# Power_Suply.net
KiCad netlist of a schematic drawn in Altium Designer
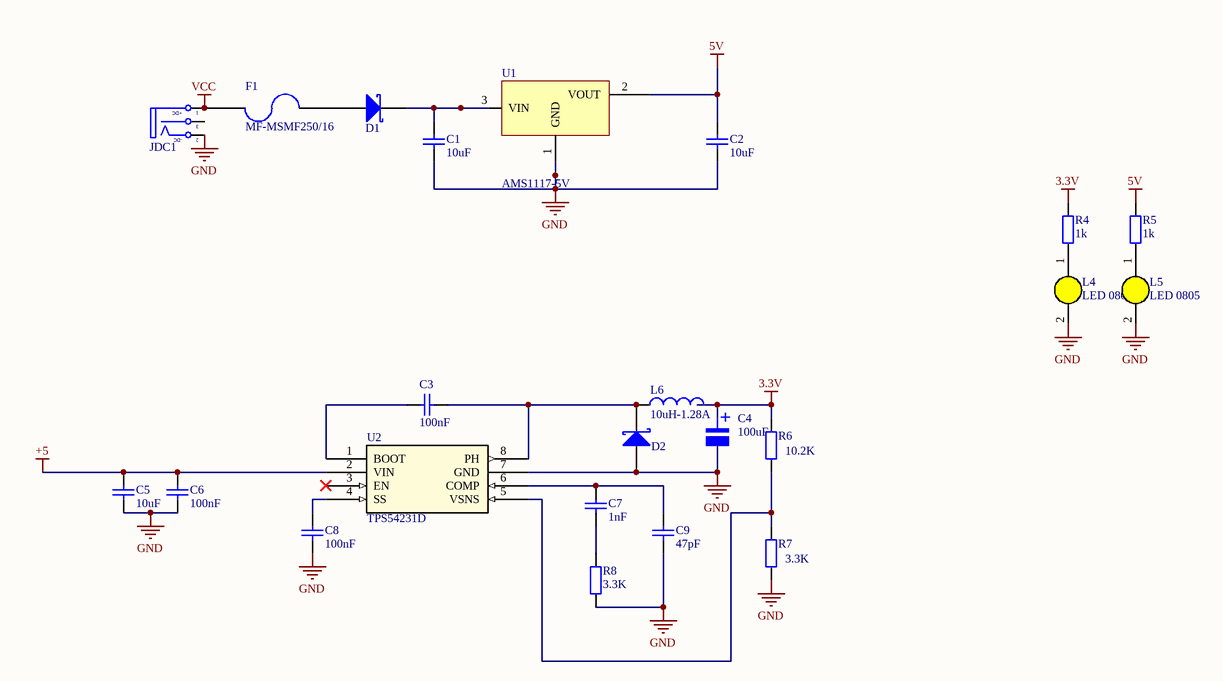
[diagram p0: Power Suply.SchDoc]

(export (version "E")
  (design (tool "Eeschema 10.0.6"))
  (components
    (comp (ref "C1")
      (value "10uF")
      (footprint "tu 0805")
      (description "Dán")
      (libsource (lib "Tu dien") (part "Tu 0805 101 50V 20%"))
    )
    (comp (ref "C2")
      (value "10uF")
      (footprint "tu 0805")
      (description "Dán")
      (libsource (lib "Tu dien") (part "Tu 0805 101 50V 20%"))
    )
    (comp (ref "C3")
      (value "100nF")
      (footprint "tu 0805")
      (description "Dán")
      (libsource (lib "Tu dien") (part "Tu 0805 106 16V 10%"))
    )
    (comp (ref "C4")
      (value "100uF")
      (footprint "tu nhom 6.3 (d)")
      (description "Dán")
      (libsource (lib "Altium_Lib_by_KhueNguyenCreator") (part "Tu Nhom 100uF 16V"))
    )
    (comp (ref "C5")
      (value "10uF")
      (footprint "tu 0805")
      (description "Dán")
      (libsource (lib "Tu dien") (part "Tu 0805 106 16V 10%"))
    )
    (comp (ref "C6")
      (value "100nF")
      (footprint "tu 0805")
      (description "Dán")
      (libsource (lib "Tu dien") (part "Tu 0805 106 16V 10%"))
    )
    (comp (ref "C7")
      (value "1nF")
      (footprint "tu 0805")
      (description "Dán")
      (libsource (lib "Tu dien") (part "Tu 0805 106 16V 10%"))
    )
    (comp (ref "C8")
      (value "100nF")
      (footprint "tu 0805")
      (description "Dán")
      (libsource (lib "Tu dien") (part "Tu 0805 106 16V 10%"))
    )
    (comp (ref "C9")
      (value "47pF")
      (footprint "tu 0805")
      (description "Dán")
      (libsource (lib "Tu dien") (part "Tu 0805 106 16V 10%"))
    )
    (comp (ref "D1")
      (value "D Schottky")
      (footprint "SS34")
      (description "Schottky Diode")
      (fields (field (name "PUBLISHER") "Altium Limited"))
      (libsource (lib "PIF_Library") (part "D Schottky"))
    )
    (comp (ref "D2")
      (value "D Schottky")
      (footprint "SS34")
      (description "Schottky Diode")
      (fields (field (name "PUBLISHER") "Altium Limited"))
      (libsource (lib "PIF_Library") (part "D Schottky"))
    )
    (comp (ref "F1")
      (value "MF-MSMF250/16")
      (footprint "MF-MSMF250/16")
      (libsource (lib "YenDoo") (part "MF-MSMF250/16"))
    )
    (comp (ref "JDC1")
      (value "Jack DC")
      (footprint "DC-IN")
      (description "Jack DC input")
      (libsource (lib "PIF_Library") (part "Jack DC"))
    )
    (comp (ref "L4")
      (value "LED 0805")
      (footprint "LED-0805-Yellow")
      (description "Dán")
      (libsource (lib "Led") (part "LED 0805 Vang"))
    )
    (comp (ref "L5")
      (value "LED 0805")
      (footprint "LED-0805-Yellow")
      (description "Dán")
      (libsource (lib "Led") (part "LED 0805 Vang"))
    )
    (comp (ref "L6")
      (value "10uH-1.28A")
      (footprint "I0805")
      (fields (field (name "Comment") "Inductor"))
      (libsource (lib "MiclsLib") (part "Inductor"))
    )
    (comp (ref "R4")
      (value "1k")
      (footprint "tro smd 0805")
      (description "Dán")
      (libsource (lib "Dien Tro") (part "Tro 0805 1% 1k"))
    )
    (comp (ref "R5")
      (value "1k")
      (footprint "tro smd 0805")
      (description "Dán")
      (libsource (lib "Dien Tro") (part "Tro 0805 1% 1k"))
    )
    (comp (ref "R6")
      (value "10.2K")
      (footprint "tro smd 0805")
      (description "Dán")
      (libsource (lib "Dien Tro") (part "Tro 0805 1% 5.1k"))
    )
    (comp (ref "R7")
      (value "3.3K")
      (footprint "tro smd 0805")
      (description "Dán")
      (libsource (lib "Dien Tro") (part "Tro 0805 1% 5.1k"))
    )
    (comp (ref "R8")
      (value "3.3K")
      (footprint "tro smd 0805")
      (description "Dán")
      (libsource (lib "Dien Tro") (part "Tro 0805 1% 5.1k"))
    )
    (comp (ref "U1")
      (value "AMS1117-5V")
      (footprint "SOT230P700X180-4N")
      (libsource (lib "MiclsLib") (part "AMS1117-5V"))
    )
    (comp (ref "U2")
      (value "TPS54231D")
      (footprint "SOIC8_50_328_25X90_SMT")
      (fields
        (field (name "MANUFACTURER") "Texas Instruments")
        (field (name "MANUFACTURER PART NUMBER") "TPS54360DDAR")
      )
      (libsource (lib "Altium_Lib_by_KhueNguyenCreator") (part "IC_TPS54360DDAR"))
    )
  )
  (nets
    (net (code "1") (name "+5") (class "Default")
      (node (ref "C5") (pin "2") (pinfunction "2_2") (pintype "passive"))
      (node (ref "C6") (pin "2") (pinfunction "2_2") (pintype "passive"))
      (node (ref "U2") (pin "2") (pinfunction "VIN_2") (pintype "power_in"))
    )
    (net (code "2") (name "3.3V") (class "Default")
      (node (ref "C4") (pin "1") (pinfunction "1_1") (pintype "passive"))
      (node (ref "L6") (pin "2") (pinfunction "2_2") (pintype "passive"))
      (node (ref "R4") (pin "2") (pinfunction "2_2") (pintype "passive"))
      (node (ref "R6") (pin "2") (pinfunction "2_2") (pintype "passive"))
    )
    (net (code "3") (name "5V") (class "Default")
      (node (ref "C2") (pin "1") (pinfunction "1_1") (pintype "passive"))
      (node (ref "R5") (pin "2") (pinfunction "2_2") (pintype "passive"))
      (node (ref "U1") (pin "2") (pinfunction "VOUT_2") (pintype "passive"))
    )
    (net (code "4") (name "GND") (class "Default")
      (node (ref "C1") (pin "2") (pinfunction "2_2") (pintype "passive"))
      (node (ref "C2") (pin "2") (pinfunction "2_2") (pintype "passive"))
      (node (ref "C4") (pin "2") (pinfunction "2_2") (pintype "passive"))
      (node (ref "C5") (pin "1") (pinfunction "1_1") (pintype "passive"))
      (node (ref "C6") (pin "1") (pinfunction "1_1") (pintype "passive"))
      (node (ref "C8") (pin "1") (pinfunction "1_1") (pintype "passive"))
      (node (ref "C9") (pin "1") (pinfunction "1_1") (pintype "passive"))
      (node (ref "D2") (pin "1") (pinfunction "A_1") (pintype "passive"))
      (node (ref "JDC1") (pin "2") (pinfunction "TN_2") (pintype "passive"))
      (node (ref "L4") (pin "2") (pinfunction "K_2") (pintype "passive"))
      (node (ref "L5") (pin "2") (pinfunction "K_2") (pintype "passive"))
      (node (ref "R7") (pin "1") (pinfunction "1_1") (pintype "passive"))
      (node (ref "R8") (pin "1") (pinfunction "1_1") (pintype "passive"))
      (node (ref "U1") (pin "1") (pinfunction "GND_1") (pintype "passive"))
      (node (ref "U2") (pin "7") (pinfunction "GND_7") (pintype "power_in"))
    )
    (net (code "5") (name "Net-(C7-Pad1)") (class "Default")
      (node (ref "C7") (pin "1") (pinfunction "1_1") (pintype "passive"))
      (node (ref "R8") (pin "2") (pinfunction "2_2") (pintype "passive"))
    )
    (net (code "6") (name "Net-(D1-A)") (class "Default")
      (node (ref "D1") (pin "1") (pinfunction "A_1") (pintype "passive"))
      (node (ref "F1") (pin "2") (pintype "passive"))
    )
    (net (code "7") (name "Net-(D1-K)") (class "Default")
      (node (ref "C1") (pin "1") (pinfunction "1_1") (pintype "passive"))
      (node (ref "D1") (pin "2") (pinfunction "K_2") (pintype "passive"))
      (node (ref "U1") (pin "3") (pinfunction "VIN_3") (pintype "passive"))
    )
    (net (code "8") (name "Net-(D2-K)") (class "Default")
      (node (ref "C3") (pin "2") (pinfunction "2_2") (pintype "passive"))
      (node (ref "D2") (pin "2") (pinfunction "K_2") (pintype "passive"))
      (node (ref "L6") (pin "1") (pinfunction "1_1") (pintype "passive"))
      (node (ref "U2") (pin "8") (pinfunction "PH_8") (pintype "output"))
    )
    (net (code "9") (name "Net-(L4-A)") (class "Default")
      (node (ref "L4") (pin "1") (pinfunction "A_1") (pintype "passive"))
      (node (ref "R4") (pin "1") (pinfunction "1_1") (pintype "passive"))
    )
    (net (code "10") (name "Net-(L5-A)") (class "Default")
      (node (ref "L5") (pin "1") (pinfunction "A_1") (pintype "passive"))
      (node (ref "R5") (pin "1") (pinfunction "1_1") (pintype "passive"))
    )
    (net (code "11") (name "Net-(U2-BOOT)") (class "Default")
      (node (ref "C3") (pin "1") (pinfunction "1_1") (pintype "passive"))
      (node (ref "U2") (pin "1") (pinfunction "BOOT_1") (pintype "passive"))
    )
    (net (code "12") (name "Net-(U2-COMP)") (class "Default")
      (node (ref "C7") (pin "2") (pinfunction "2_2") (pintype "passive"))
      (node (ref "C9") (pin "2") (pinfunction "2_2") (pintype "passive"))
      (node (ref "U2") (pin "6") (pinfunction "COMP_6") (pintype "input"))
    )
    (net (code "13") (name "Net-(U2-SS)") (class "Default")
      (node (ref "C8") (pin "2") (pinfunction "2_2") (pintype "passive"))
      (node (ref "U2") (pin "4") (pinfunction "SS_4") (pintype "input"))
    )
    (net (code "14") (name "Net-(U2-VSNS)") (class "Default")
      (node (ref "R6") (pin "1") (pinfunction "1_1") (pintype "passive"))
      (node (ref "R7") (pin "2") (pinfunction "2_2") (pintype "passive"))
      (node (ref "U2") (pin "5") (pinfunction "VSNS_5") (pintype "input"))
    )
    (net (code "15") (name "VCC") (class "Default")
      (node (ref "F1") (pin "1") (pintype "passive"))
      (node (ref "JDC1") (pin "1") (pinfunction "T_1") (pintype "passive"))
    )
    (net (code "16") (name "unconnected-(JDC1-S-Pad3)") (class "Default")
      (node (ref "JDC1") (pin "3") (pinfunction "S_3") (pintype "power_in"))
    )
    (net (code "17") (name "unconnected-(U2-EN-Pad3)") (class "Default")
      (node (ref "U2") (pin "3") (pinfunction "EN_3") (pintype "input+no_connect"))
    )
  )
)
